# 20-RGMII_ETHERNET_PHY_-_ICSSG_PRG2_PRU0.net
KiCad netlist of a schematic drawn in Altium Designer
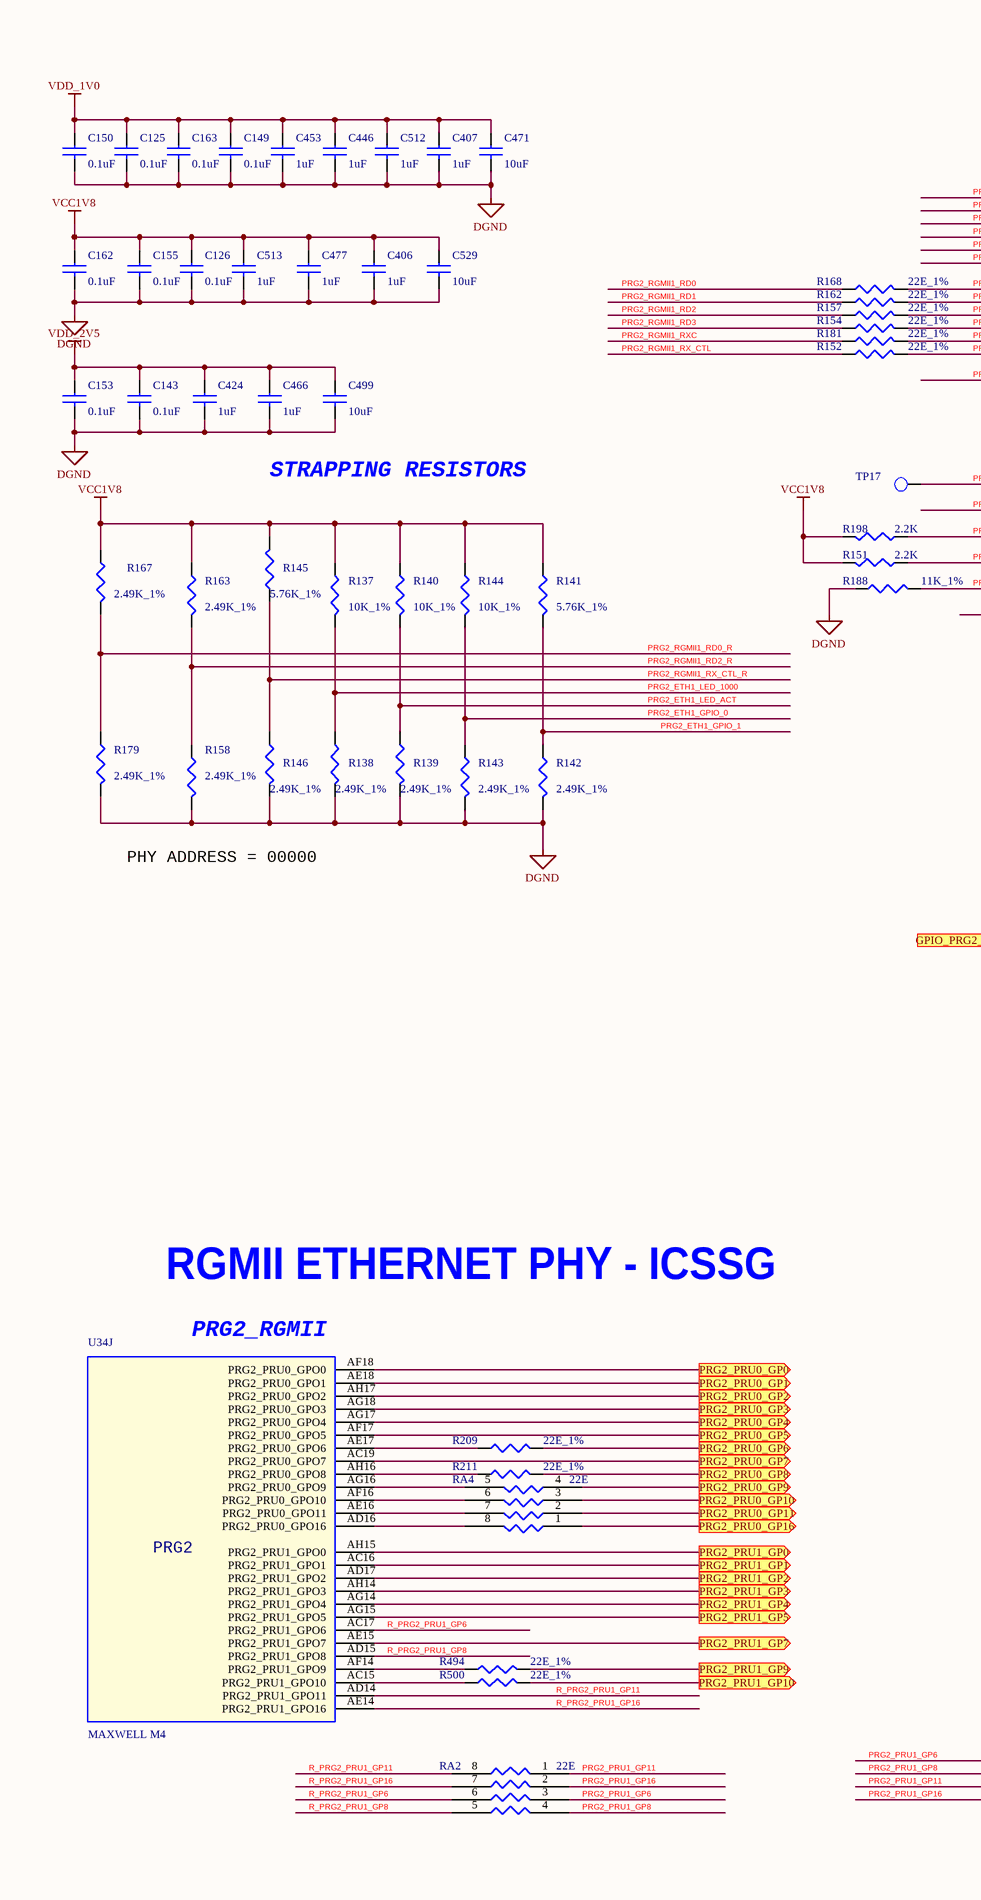
[diagram p0: 20-RGMII ETHERNET PHY - ICSSG PRG2_PRU0.SchDoc, left]
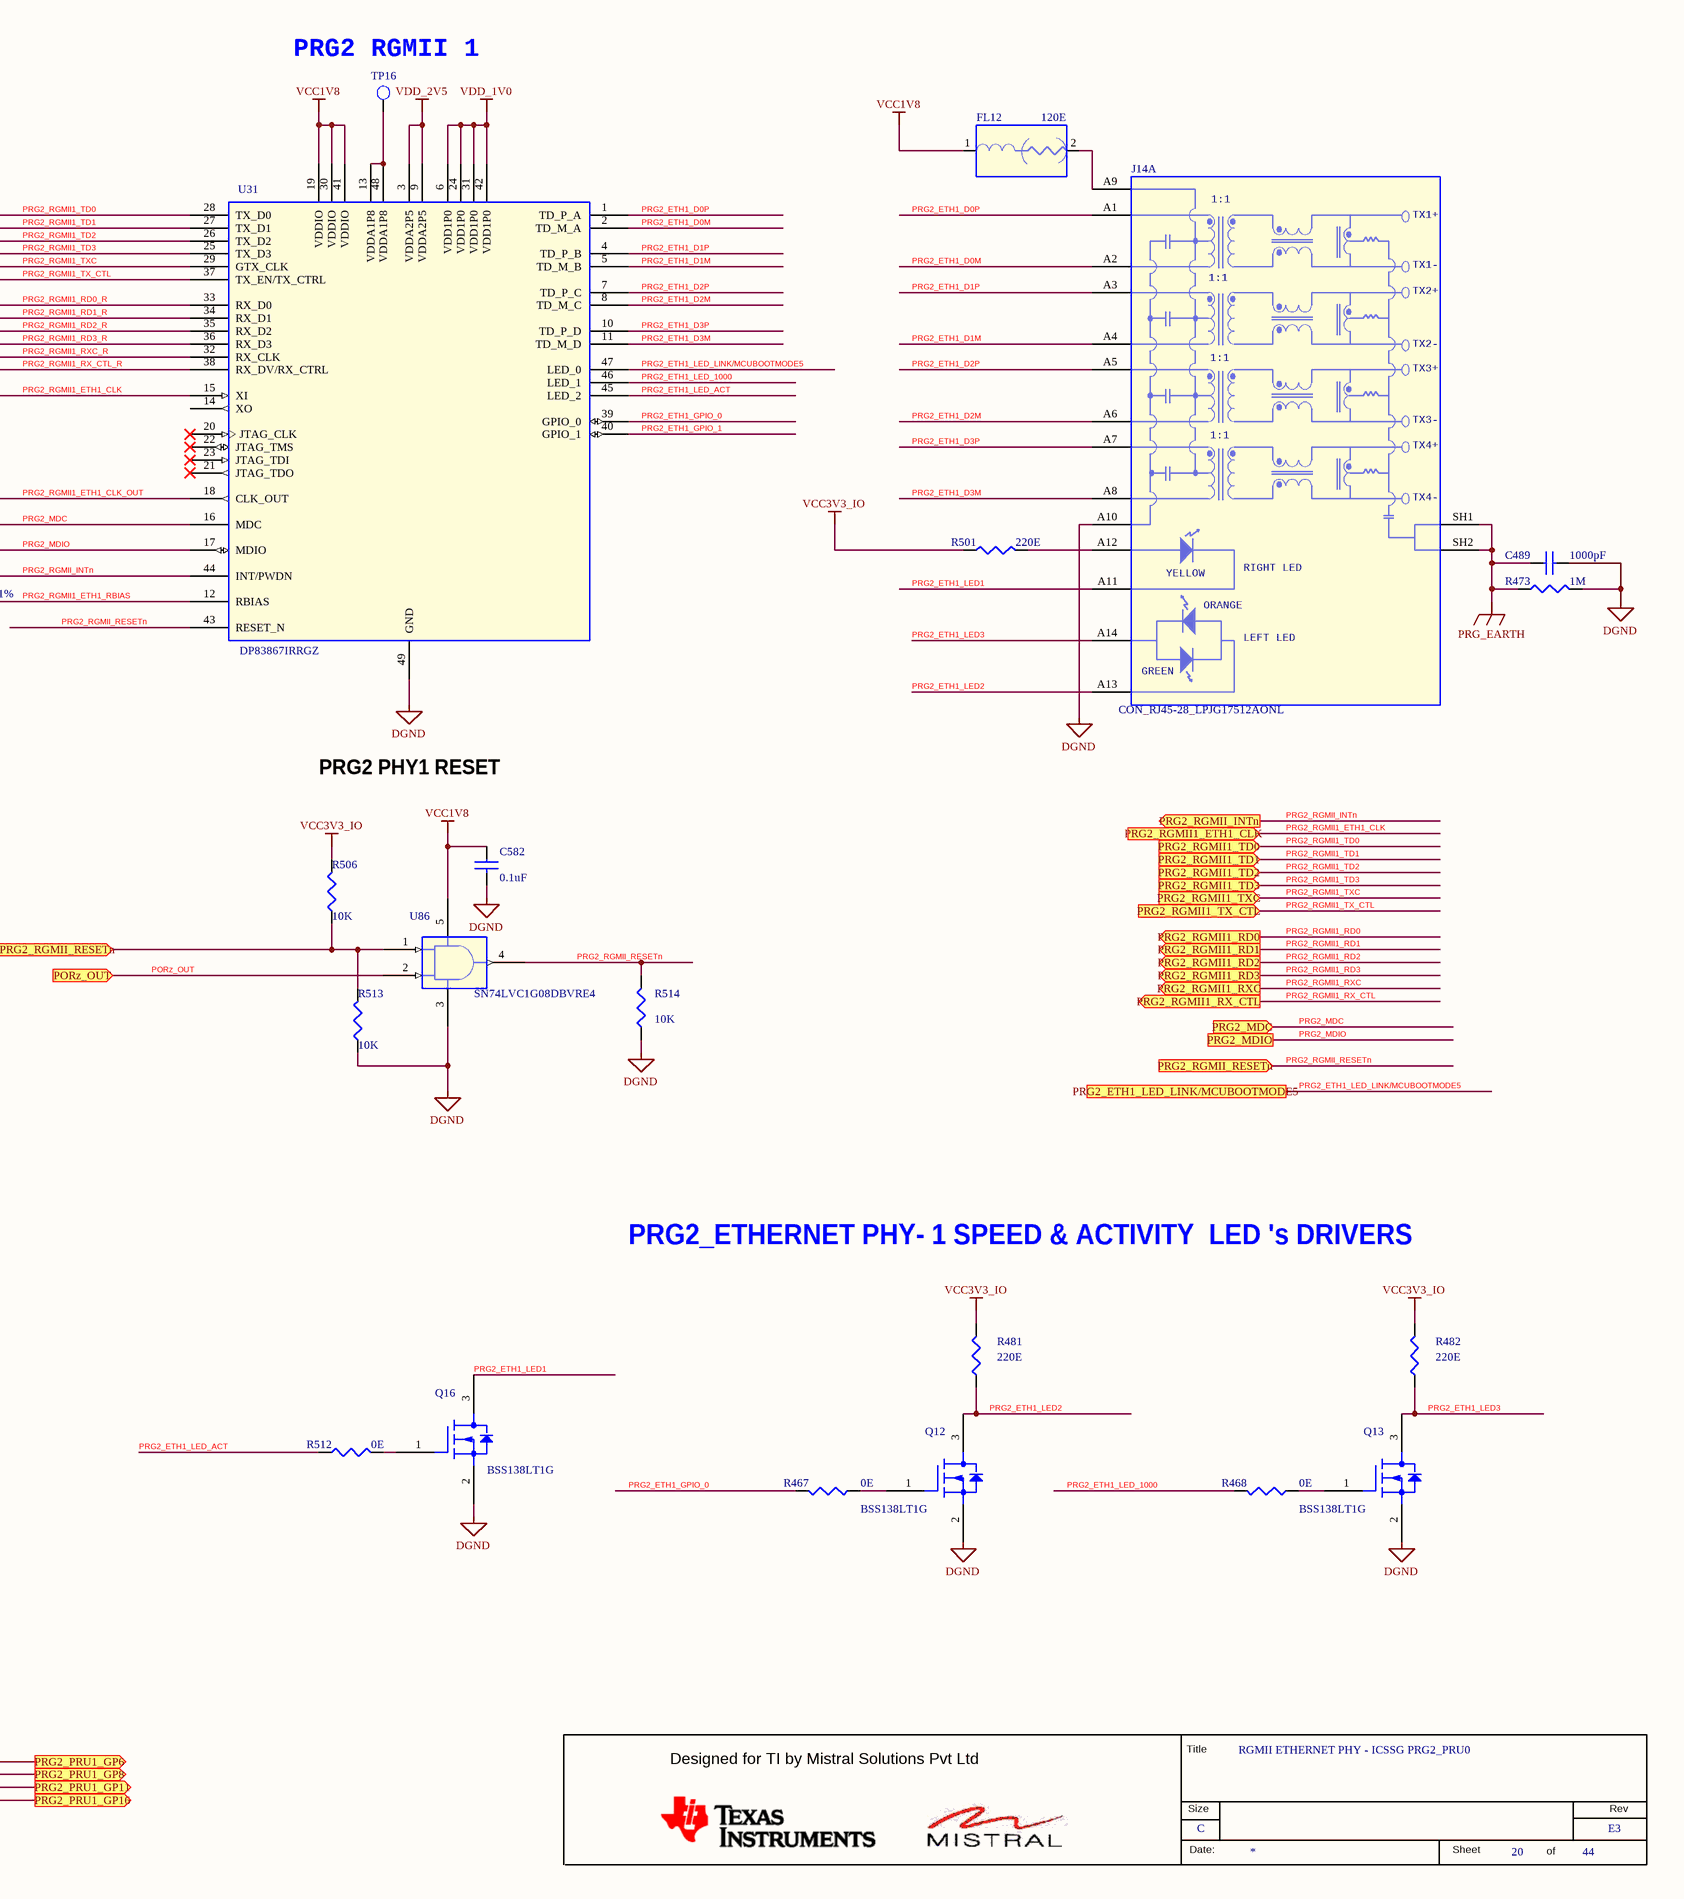
[diagram p1: 20-RGMII ETHERNET PHY - ICSSG PRG2_PRU0.SchDoc, right]

(export (version "E")
  (design (tool "Eeschema 10.0.6"))
  (components
    (comp (ref "C125")
      (value "0.1uF")
      (footprint "CAP0201_0-5")
      (description "CAP CERAMIC 0.1uF 16V 10% X5R 0201")
      (fields (field (name "DISTRIBUTOR_PART_NUMBER") "490-16742-1-ND") (field (name "VOLTAGE") "16V"))
      (libsource (lib "*") (part "CAP_Dup5"))
    )
    (comp (ref "C126")
      (value "0.1uF")
      (footprint "CAP0201_0-5")
      (description "CAP CERAMIC 0.1uF 16V 10% X5R 0201")
      (fields
        (field (name "MISTRAL PART NO") "120009030072-R")
        (field (name "MFR_PART_NUMBER") "GRM033R61C104KE84J")
      )
      (libsource (lib "*") (part "CAP_Dup5"))
    )
    (comp (ref "C143")
      (value "0.1uF")
      (footprint "CAP0201_0-5")
      (description "CAP CERAMIC 0.1uF 16V 10% X5R 0201")
      (fields
        (field (name "MISTRAL PART NO") "120009030072-R")
        (field (name "MFR_PART_NUMBER") "GRM033R61C104KE84J")
      )
      (libsource (lib "*") (part "CAP_Dup5"))
    )
    (comp (ref "C149")
      (value "0.1uF")
      (footprint "CAP0201_0-5")
      (description "CAP CERAMIC 0.1uF 16V 10% X5R 0201")
      (fields
        (field (name "MISTRAL PART NO") "120009030072-R")
        (field (name "MFR_PART_NUMBER") "GRM033R61C104KE84J")
      )
      (libsource (lib "*") (part "CAP_Dup5"))
    )
    (comp (ref "C150")
      (value "0.1uF")
      (footprint "CAP0201_0-5")
      (description "CAP CERAMIC 0.1uF 16V 10% X5R 0201")
      (fields (field (name "DISTRIBUTOR_PART_NUMBER") "490-16742-1-ND") (field (name "VOLTAGE") "16V"))
      (libsource (lib "*") (part "CAP_Dup5"))
    )
    (comp (ref "C153")
      (value "0.1uF")
      (footprint "CAP0201_0-5")
      (description "CAP CERAMIC 0.1uF 16V 10% X5R 0201")
      (fields (field (name "DISTRIBUTOR_PART_NUMBER") "490-16742-1-ND") (field (name "VOLTAGE") "16V"))
      (libsource (lib "*") (part "CAP_Dup5"))
    )
    (comp (ref "C155")
      (value "0.1uF")
      (footprint "CAP0201_0-5")
      (description "CAP CERAMIC 0.1uF 16V 10% X5R 0201")
      (fields
        (field (name "MISTRAL PART NO") "120009030072-R")
        (field (name "MFR_PART_NUMBER") "GRM033R61C104KE84J")
      )
      (libsource (lib "*") (part "CAP_Dup5"))
    )
    (comp (ref "C162")
      (value "0.1uF")
      (footprint "CAP0201_0-5")
      (description "CAP CERAMIC 0.1uF 16V 10% X5R 0201")
      (fields
        (field (name "MISTRAL PART NO") "120009030072-R")
        (field (name "MFR_PART_NUMBER") "GRM033R61C104KE84J")
      )
      (libsource (lib "*") (part "CAP_Dup5"))
    )
    (comp (ref "C163")
      (value "0.1uF")
      (footprint "CAP0201_0-5")
      (description "CAP CERAMIC 0.1uF 16V 10% X5R 0201")
      (fields
        (field (name "MISTRAL PART NO") "120009030072-R")
        (field (name "MFR_PART_NUMBER") "GRM033R61C104KE84J")
      )
      (libsource (lib "*") (part "CAP_Dup5"))
    )
    (comp (ref "C406")
      (value "1uF")
      (footprint "CAP0402_0-75")
      (description "CAP CERAMIC 1uF 16V 20% X5R 0402")
      (fields
        (field (name "MISTRAL PART NO") "120018020006-R")
        (field (name "MFR_PART_NUMBER") "EMK105BJ105MV-F")
      )
      (libsource (lib "*") (part "CAP_Dup5"))
    )
    (comp (ref "C407")
      (value "1uF")
      (footprint "CAP0402_0-75")
      (description "CAP CERAMIC 1uF 16V 20% X5R 0402")
      (fields
        (field (name "MISTRAL PART NO") "120018020006-R")
        (field (name "MFR_PART_NUMBER") "EMK105BJ105MV-F")
      )
      (libsource (lib "*") (part "CAP_Dup5"))
    )
    (comp (ref "C424")
      (value "1uF")
      (footprint "CAP0402_0-75")
      (description "CAP CERAMIC 1uF 16V 20% X5R 0402")
      (fields (field (name "DISTRIBUTOR_PART_NUMBER") "587-5514-1-ND") (field (name "VOLTAGE") "16V"))
      (libsource (lib "*") (part "CAP_Dup5"))
    )
    (comp (ref "C446")
      (value "1uF")
      (footprint "CAP0402_0-75")
      (description "CAP CERAMIC 1uF 16V 20% X5R 0402")
      (fields
        (field (name "MISTRAL PART NO") "120018020006-R")
        (field (name "MFR_PART_NUMBER") "EMK105BJ105MV-F")
      )
      (libsource (lib "*") (part "CAP_Dup5"))
    )
    (comp (ref "C453")
      (value "1uF")
      (footprint "CAP0402_0-75")
      (description "CAP CERAMIC 1uF 16V 20% X5R 0402")
      (fields (field (name "DISTRIBUTOR_PART_NUMBER") "587-5514-1-ND") (field (name "VOLTAGE") "16V"))
      (libsource (lib "*") (part "CAP_Dup5"))
    )
    (comp (ref "C466")
      (value "1uF")
      (footprint "CAP0402_0-75")
      (description "CAP CERAMIC 1uF 16V 20% X5R 0402")
      (fields (field (name "DISTRIBUTOR_PART_NUMBER") "587-5514-1-ND") (field (name "VOLTAGE") "16V"))
      (libsource (lib "*") (part "CAP_Dup5"))
    )
    (comp (ref "C471")
      (value "10uF")
      (footprint "CAP0603_1")
      (description "CAP CERAMIC 10uF 10V 10% X5R 0603")
      (fields
        (field (name "MISTRAL PART NO") "120010080001-R")
        (field (name "MFR_PART_NUMBER") "0603ZD106KAT2A")
      )
      (libsource (lib "*") (part "CAP_Dup5"))
    )
    (comp (ref "C477")
      (value "1uF")
      (footprint "CAP0402_0-75")
      (description "CAP CERAMIC 1uF 16V 20% X5R 0402")
      (fields
        (field (name "MISTRAL PART NO") "120018020006-R")
        (field (name "MFR_PART_NUMBER") "EMK105BJ105MV-F")
      )
      (libsource (lib "*") (part "CAP_Dup5"))
    )
    (comp (ref "C489")
      (value "1000pF")
      (footprint "CAP1206")
      (description "CAP CERAMIC 1000pF 2KV 10% X7R 1206")
      (fields
        (field (name "MISTRAL PART NO") "120009030147-R")
        (field (name "MFR_PART_NUMBER") "1206GC102KAT1A")
      )
      (libsource (lib "*") (part "CAP_Dup5"))
    )
    (comp (ref "C499")
      (value "10uF")
      (footprint "CAP0603_1")
      (description "CAP CERAMIC 10uF 10V 10% X5R 0603")
      (fields (field (name "DISTRIBUTOR_PART_NUMBER") "478-10766-1-ND") (field (name "VOLTAGE") "10V"))
      (libsource (lib "*") (part "CAP_Dup5"))
    )
    (comp (ref "C512")
      (value "1uF")
      (footprint "CAP0402_0-75")
      (description "CAP CERAMIC 1uF 16V 20% X5R 0402")
      (fields (field (name "DISTRIBUTOR_PART_NUMBER") "587-5514-1-ND") (field (name "VOLTAGE") "16V"))
      (libsource (lib "*") (part "CAP_Dup5"))
    )
    (comp (ref "C513")
      (value "1uF")
      (footprint "CAP0402_0-75")
      (description "CAP CERAMIC 1uF 16V 20% X5R 0402")
      (fields
        (field (name "MISTRAL PART NO") "120018020006-R")
        (field (name "MFR_PART_NUMBER") "EMK105BJ105MV-F")
      )
      (libsource (lib "*") (part "CAP_Dup5"))
    )
    (comp (ref "C529")
      (value "10uF")
      (footprint "CAP0603_1")
      (description "CAP CERAMIC 10uF 10V 10% X5R 0603")
      (fields
        (field (name "MISTRAL PART NO") "120010080001-R")
        (field (name "MFR_PART_NUMBER") "0603ZD106KAT2A")
      )
      (libsource (lib "*") (part "CAP_Dup5"))
    )
    (comp (ref "C582")
      (value "0.1uF")
      (footprint "CAP0201_0-5")
      (description "CAP CERAMIC 0.1uF 16V 10% X5R 0201")
      (fields (field (name "DISTRIBUTOR_PART_NUMBER") "490-16742-1-ND") (field (name "VOLTAGE") "16V"))
      (libsource (lib "*") (part "CAP_Dup5"))
    )
    (comp (ref "FL12")
      (value "120E")
      (footprint "EMIFIL_BLM15A_0402_0-6")
      (description "FERRITE CHIP 120E 1.3A 0402")
      (fields (field (name "DISTRIBUTOR_PART_NUMBER") "490-5203-1-ND") (field (name "VOLTAGE") "NA"))
      (libsource (lib "*") (part "EMIFILTER_IND"))
    )
    (comp (ref "J14")
      (value "CON_RJ45-28_LPJG17512AONL")
      (footprint "CON_RJ45-28_LPJG17512_S_R_T_25-3")
      (description "CON JACK RJ45 28POS REGISTERED FEMALE RA TH")
      (fields (field (name "DISTRIBUTOR_PART_NUMBER") "NA") (field (name "MFR_PART_NUMBER") "LPJG17512AONL"))
      (libsource (lib "*") (part "CON_RJ45-28_LPJG17512AONL"))
    )
    (comp (ref "Q12")
      (value "BSS138LT1G")
      (footprint "SOT23-123")
      (description "IC MOSFET N-CHANNEL 50V, SOT23-3")
      (fields (field (name "DISTRIBUTOR_PART_NUMBER") "863-BSS138LT1G") (field (name "VOLTAGE") "50V"))
      (libsource (lib "*") (part "MOSFET_BSS138LT1G"))
    )
    (comp (ref "Q13")
      (value "BSS138LT1G")
      (footprint "SOT23-123")
      (description "IC MOSFET N-CHANNEL 50V, SOT23-3")
      (fields (field (name "MISTRAL PART NO") "142016040001-R") (field (name "TOLERANCE") "NA"))
      (libsource (lib "*") (part "MOSFET_BSS138LT1G"))
    )
    (comp (ref "Q16")
      (value "BSS138LT1G")
      (footprint "SOT23-123")
      (description "IC MOSFET N-CHANNEL 50V, SOT23-3")
      (fields (field (name "DISTRIBUTOR_PART_NUMBER") "863-BSS138LT1G") (field (name "VOLTAGE") "50V"))
      (libsource (lib "*") (part "MOSFET_BSS138LT1G"))
    )
    (comp (ref "R137")
      (value "10K_1%")
      (footprint "RES0402_0-5")
      (description "RES 10K 1/16W 1% 0402")
      (fields
        (field (name "MISTRAL PART NO") "110009030220-P")
        (field (name "MFR_PART_NUMBER") "RC0402FR-0710KL")
      )
      (libsource (lib "*") (part "RESISTOR_Dup5"))
    )
    (comp (ref "R138")
      (value "2.49K_1%")
      (footprint "RES0402")
      (description "RES 2.49K 1/16W 1% 0402")
      (fields
        (field (name "MISTRAL PART NO") "110016050020-R")
        (field (name "MFR_PART_NUMBER") "RC0402FR-072K49L")
      )
      (libsource (lib "*") (part "RESISTOR_Dup5"))
    )
    (comp (ref "R139")
      (value "2.49K_1%")
      (footprint "RES0402")
      (description "RES 2.49K 1/16W 1% 0402")
      (fields
        (field (name "MISTRAL PART NO") "110016050020-R")
        (field (name "MFR_PART_NUMBER") "RC0402FR-072K49L")
      )
      (libsource (lib "*") (part "RESISTOR_Dup5"))
    )
    (comp (ref "R140")
      (value "10K_1%")
      (footprint "RES0402_0-5")
      (description "RES 10K 1/16W 1% 0402")
      (fields
        (field (name "MISTRAL PART NO") "110009030220-P")
        (field (name "MFR_PART_NUMBER") "RC0402FR-0710KL")
      )
      (libsource (lib "*") (part "RESISTOR_Dup5"))
    )
    (comp (ref "R141")
      (value "5.76K_1%")
      (footprint "RES0402")
      (description "RES 5.76K 1/10W 1% 0402")
      (fields (field (name "DISTRIBUTOR_PART_NUMBER") "P5.76KLCT-ND") (field (name "TOLERANCE") "1%"))
      (libsource (lib "*") (part "RESISTOR_Dup5"))
    )
    (comp (ref "R142")
      (value "2.49K_1%")
      (footprint "RES0402")
      (description "RES 2.49K 1/16W 1% 0402")
      (fields (field (name "DISTRIBUTOR_PART_NUMBER") "311-2.49KLRCT-ND") (field (name "VOLTAGE") "NA"))
      (libsource (lib "*") (part "RESISTOR_Dup5"))
    )
    (comp (ref "R143")
      (value "2.49K_1%")
      (footprint "RES0402")
      (description "RES 2.49K 1/16W 1% 0402")
      (fields (field (name "DISTRIBUTOR_PART_NUMBER") "311-2.49KLRCT-ND") (field (name "VOLTAGE") "NA"))
      (libsource (lib "*") (part "RESISTOR_Dup5"))
    )
    (comp (ref "R144")
      (value "10K_1%")
      (footprint "RES0402_0-5")
      (description "RES 10K 1/16W 1% 0402")
      (fields (field (name "DISTRIBUTOR_PART_NUMBER") "311-10.0KLRTR-ND") (field (name "VOLTAGE") "NA"))
      (libsource (lib "*") (part "RESISTOR_Dup5"))
    )
    (comp (ref "R145")
      (value "5.76K_1%")
      (footprint "RES0402")
      (description "RES 5.76K 1/10W 1% 0402")
      (fields
        (field (name "MISTRAL PART NO") "110009030945-R")
        (field (name "MFR_PART_NUMBER") "ERJ-2RKF5761X")
      )
      (libsource (lib "*") (part "RESISTOR_Dup5"))
    )
    (comp (ref "R146")
      (value "2.49K_1%")
      (footprint "RES0402")
      (description "RES 2.49K 1/16W 1% 0402")
      (fields (field (name "DISTRIBUTOR_PART_NUMBER") "311-2.49KLRCT-ND") (field (name "VOLTAGE") "NA"))
      (libsource (lib "*") (part "RESISTOR_Dup5"))
    )
    (comp (ref "R151")
      (value "2.2K")
      (footprint "RES0402_0-5")
      (description "RES 2.2K 1/16W 5% 0402")
      (fields
        (field (name "MISTRAL PART NO") "110010120018-R")
        (field (name "MFR_PART_NUMBER") "RC0402JR-072K2L")
      )
      (libsource (lib "*") (part "RESISTOR_Dup5"))
    )
    (comp (ref "R152")
      (value "22E_1%")
      (footprint "RES0402")
      (description "RES 22E 1/16W 1% 0402")
      (fields
        (field (name "MISTRAL PART NO") "110009090004-P")
        (field (name "MFR_PART_NUMBER") "RC0402FR-0722RL")
      )
      (libsource (lib "*") (part "RESISTOR_Dup5"))
    )
    (comp (ref "R154")
      (value "22E_1%")
      (footprint "RES0402")
      (description "RES 22E 1/16W 1% 0402")
      (fields
        (field (name "CUST_PART_NUMBER") "4700-80047E")
        (field (name "DISTRIBUTOR_PART_NUMBER") "311-22.0LRCT-ND")
      )
      (libsource (lib "*") (part "RESISTOR_Dup5"))
    )
    (comp (ref "R157")
      (value "22E_1%")
      (footprint "RES0402")
      (description "RES 22E 1/16W 1% 0402")
      (fields
        (field (name "MISTRAL PART NO") "110009090004-P")
        (field (name "MFR_PART_NUMBER") "RC0402FR-0722RL")
      )
      (libsource (lib "*") (part "RESISTOR_Dup5"))
    )
    (comp (ref "R158")
      (value "2.49K_1%")
      (footprint "RES0402")
      (description "RES 2.49K 1/16W 1% 0402")
      (fields (field (name "DISTRIBUTOR_PART_NUMBER") "311-2.49KLRCT-ND") (field (name "VOLTAGE") "NA"))
      (libsource (lib "*") (part "RESISTOR_Dup5"))
    )
    (comp (ref "R162")
      (value "22E_1%")
      (footprint "RES0402")
      (description "RES 22E 1/16W 1% 0402")
      (fields
        (field (name "CUST_PART_NUMBER") "4700-80047E")
        (field (name "DISTRIBUTOR_PART_NUMBER") "311-22.0LRCT-ND")
      )
      (libsource (lib "*") (part "RESISTOR_Dup5"))
    )
    (comp (ref "R163")
      (value "2.49K_1%")
      (footprint "RES0402")
      (description "RES 2.49K 1/16W 1% 0402")
      (fields (field (name "DISTRIBUTOR_PART_NUMBER") "311-2.49KLRCT-ND") (field (name "VOLTAGE") "NA"))
      (libsource (lib "*") (part "RESISTOR_Dup5"))
    )
    (comp (ref "R167")
      (value "2.49K_1%")
      (footprint "RES0402")
      (description "RES 2.49K 1/16W 1% 0402")
      (fields (field (name "DISTRIBUTOR_PART_NUMBER") "311-2.49KLRCT-ND") (field (name "VOLTAGE") "NA"))
      (libsource (lib "*") (part "RESISTOR_Dup5"))
    )
    (comp (ref "R168")
      (value "22E_1%")
      (footprint "RES0402")
      (description "RES 22E 1/16W 1% 0402")
      (fields
        (field (name "MISTRAL PART NO") "110009090004-P")
        (field (name "MFR_PART_NUMBER") "RC0402FR-0722RL")
      )
      (libsource (lib "*") (part "RESISTOR_Dup5"))
    )
    (comp (ref "R179")
      (value "2.49K_1%")
      (footprint "RES0402")
      (description "RES 2.49K 1/16W 1% 0402")
      (fields
        (field (name "MISTRAL PART NO") "110016050020-R")
        (field (name "MFR_PART_NUMBER") "RC0402FR-072K49L")
      )
      (libsource (lib "*") (part "RESISTOR_Dup5"))
    )
    (comp (ref "R181")
      (value "22E_1%")
      (footprint "RES0402")
      (description "RES 22E 1/16W 1% 0402")
      (fields
        (field (name "CUST_PART_NUMBER") "4700-80047E")
        (field (name "DISTRIBUTOR_PART_NUMBER") "311-22.0LRCT-ND")
      )
      (libsource (lib "*") (part "RESISTOR_Dup5"))
    )
    (comp (ref "R188")
      (value "11K_1%")
      (footprint "RES0402_0-5")
      (description "RES 11K 1/16W 1% 0402")
      (fields
        (field (name "MISTRAL PART NO") "110015110012-P")
        (field (name "MFR_PART_NUMBER") "RC0402FR-0711KL")
      )
      (libsource (lib "*") (part "RESISTOR_Dup5"))
    )
    (comp (ref "R198")
      (value "2.2K")
      (footprint "RES0402_0-5")
      (description "RES 2.2K 1/16W 5% 0402")
      (fields (field (name "DISTRIBUTOR_PART_NUMBER") "311-2.2KJRCT-ND") (field (name "VOLTAGE") "NA"))
      (libsource (lib "*") (part "RESISTOR_Dup5"))
    )
    (comp (ref "R209")
      (value "22E_1%")
      (footprint "RES0402")
      (description "RES 22E 1/16W 1% 0402")
      (fields
        (field (name "MISTRAL PART NO") "110009090004-P")
        (field (name "MFR_PART_NUMBER") "RC0402FR-0722RL")
      )
      (libsource (lib "*") (part "RESISTOR_Dup5"))
    )
    (comp (ref "R211")
      (value "22E_1%")
      (footprint "RES0402")
      (description "RES 22E 1/16W 1% 0402")
      (fields
        (field (name "CUST_PART_NUMBER") "4700-80047E")
        (field (name "DISTRIBUTOR_PART_NUMBER") "311-22.0LRCT-ND")
      )
      (libsource (lib "*") (part "RESISTOR_Dup5"))
    )
    (comp (ref "R467")
      (value "0E")
      (footprint "RES0402_0-5")
      (description "RES 0E 1/16W 0402")
      (fields (field (name "DISTRIBUTOR_PART_NUMBER") "541-0.0JCT-ND") (field (name "VOLTAGE") "NA"))
      (libsource (lib "*") (part "RESISTOR_Dup4"))
    )
    (comp (ref "R468")
      (value "0E")
      (footprint "RES0402_0-5")
      (description "RES 0E 1/16W 0402")
      (fields
        (field (name "MISTRAL PART NO") "110010080019-P")
        (field (name "MFR_PART_NUMBER") "CRCW04020000Z0ED")
      )
      (libsource (lib "*") (part "RESISTOR_Dup4"))
    )
    (comp (ref "R473")
      (value "1M")
      (footprint "RES0603_0-75")
      (description "RES 1M 1/10W 5% 0603")
      (fields (field (name "DISTRIBUTOR_PART_NUMBER") "P1.0MGCT-ND") (field (name "VOLTAGE") "NA"))
      (libsource (lib "*") (part "RESISTOR_Dup5"))
    )
    (comp (ref "R481")
      (value "220E")
      (footprint "RES0402_0-5")
      (description "RES 220E 1/16W 5% 0402")
      (fields (field (name "VOLTAGE") "NA") (field (name "DISTRIBUTOR_PART_NUMBER") "P220JCT-ND"))
      (libsource (lib "*") (part "RESISTOR_Dup5"))
    )
    (comp (ref "R482")
      (value "220E")
      (footprint "RES0402_0-5")
      (description "RES 220E 1/16W 5% 0402")
      (fields (field (name "VOLTAGE") "NA") (field (name "MISTRAL PART NO") "110009030506-R"))
      (libsource (lib "*") (part "RESISTOR_Dup5"))
    )
    (comp (ref "R494")
      (value "22E_1%")
      (footprint "RES0402")
      (description "RES 22E 1/16W 1% 0402")
      (fields
        (field (name "CUST_PART_NUMBER") "4700-80047E")
        (field (name "DISTRIBUTOR_PART_NUMBER") "311-22.0LRCT-ND")
      )
      (libsource (lib "*") (part "RESISTOR_Dup5"))
    )
    (comp (ref "R500")
      (value "22E_1%")
      (footprint "RES0402")
      (description "RES 22E 1/16W 1% 0402")
      (fields
        (field (name "MISTRAL PART NO") "110009090004-P")
        (field (name "MFR_PART_NUMBER") "RC0402FR-0722RL")
      )
      (libsource (lib "*") (part "RESISTOR_Dup5"))
    )
    (comp (ref "R501")
      (value "220E")
      (footprint "RES0402_0-5")
      (description "RES 220E 1/16W 5% 0402")
      (fields (field (name "VOLTAGE") "NA") (field (name "MISTRAL PART NO") "110009030506-R"))
      (libsource (lib "*") (part "RESISTOR_Dup5"))
    )
    (comp (ref "R506")
      (value "10K")
      (footprint "RES0402_0-5")
      (description "RES 10K 1/16W 5% 0402")
      (fields
        (field (name "MISTRAL PART NO") "110009030208-R")
        (field (name "MFR_PART_NUMBER") "RC0402JR-0710KL")
      )
      (libsource (lib "*") (part "RESISTOR_Dup5"))
    )
    (comp (ref "R512")
      (value "0E")
      (footprint "RES0402_0-5")
      (description "RES 0E 1/16W 0402")
      (fields
        (field (name "MISTRAL PART NO") "110010080019-P")
        (field (name "MFR_PART_NUMBER") "CRCW04020000Z0ED")
      )
      (libsource (lib "*") (part "RESISTOR_Dup4"))
    )
    (comp (ref "R513")
      (value "10K")
      (footprint "RES0402_0-5")
      (description "RES 10K 1/16W 5% 0402")
      (fields
        (field (name "MISTRAL PART NO") "110009030208-R")
        (field (name "MFR_PART_NUMBER") "RC0402JR-0710KL")
      )
      (libsource (lib "*") (part "RESISTOR_Dup5"))
    )
    (comp (ref "R514")
      (value "10K")
      (footprint "RES0402_0-5")
      (description "RES 10K 1/16W 5% 0402")
      (fields (field (name "DISTRIBUTOR_PART_NUMBER") "311-10KJRCT-ND") (field (name "VOLTAGE") "NA"))
      (libsource (lib "*") (part "RESISTOR_Dup5"))
    )
    (comp (ref "RA2")
      (value "22E")
      (footprint "RESA_EXB28V_0402-4_0-5")
      (description "RES ARRAY 22E 31mW 5% 0402")
      (fields (field (name "DISTRIBUTOR_PART_NUMBER") "Y7220CT-ND") (field (name "VOLTAGE") "NA"))
      (libsource (lib "*") (part "RESARR_ISO4"))
    )
    (comp (ref "RA4")
      (value "22E")
      (footprint "RESA_EXB28V_0402-4_0-5")
      (description "RES ARRAY 22E 31mW 5% 0402")
      (fields (field (name "DISTRIBUTOR_PART_NUMBER") "Y7220CT-ND") (field (name "VOLTAGE") "NA"))
      (libsource (lib "*") (part "RESARR_ISO4"))
    )
    (comp (ref "TP16")
      (value "TP40_SMD")
      (footprint "TP40_SMD")
      (description "TESTPOINT CIR 40 SMD")
      (fields (field (name "VOLTAGE") "NA") (field (name "MISTRAL PART NO") "130009030933"))
      (libsource (lib "*") (part "TESTPOINT"))
    )
    (comp (ref "TP17")
      (value "TP40_SMD")
      (footprint "TP40_SMD")
      (description "TESTPOINT CIR 40 SMD")
      (fields (field (name "DISTRIBUTOR_PART_NUMBER") "NA") (field (name "MISTRAL PART NO") "130009030933"))
      (libsource (lib "*") (part "TESTPOINT"))
    )
    (comp (ref "U31")
      (value "DP83867IRRGZ")
      (footprint "QFN48_19-68_280X280_1")
      (description "IC HIGH IMMUNITY 10/100/1000 Mb/s ETHERNET PHY LAYER TRANSCEIVER VQFN48")
      (fields (field (name "DISTRIBUTOR_PART_NUMBER") "DP83867IRRGZT-ND") (field (name "VOLTAGE") "NA"))
      (libsource (lib "*") (part "DP83867IRRGZ_VQFN48"))
    )
    (comp (ref "U34")
      (value "MAXWELL M4")
      (footprint "BGA784_31-49_910X910_1-7")
      (description "IC MAXWELL MICRO CONTROLLER UNIT BGA784")
      (fields (field (name "DISTRIBUTOR_PART_NUMBER") "NA") (field (name "MFR_PART_NUMBER") "MAXWELL M4_EVM"))
      (libsource (lib "*") (part "AM654X_BGA784"))
    )
    (comp (ref "U86")
      (value "SN74LVC1G08DBVRE4")
      (footprint "SOT23-5")
      (description "IC SINGLE 2-INPUT POSITIVE AND GATE SOT23-5")
      (fields
        (field (name "DISTRIBUTOR_PART_NUMBER") "SN74LVC1G08DBVRE4-ND")
        (field (name "MISTRAL PART NO") "141009060026-R")
      )
      (libsource (lib "*") (part "SN74LVC1G08DBVRE4_SOT23-5"))
    )
  )
  (nets
    (net (code "1") (name "/GPIO_PRG2_RGMII_RESETn") (class "Default")
      (node (ref "R506") (pin "1") (pinfunction "1_1") (pintype "passive"))
      (node (ref "R513") (pin "2") (pinfunction "2_2") (pintype "passive"))
      (node (ref "U86") (pin "1") (pinfunction "A_1") (pintype "input"))
    )
    (net (code "2") (name "/PORz_OUT") (class "Default")
      (node (ref "U86") (pin "2") (pinfunction "B_2") (pintype "input"))
    )
    (net (code "3") (name "/PRG2_ETH1_D0M") (class "Default")
      (node (ref "J14") (pin "A2") (pinfunction "TD1-_1_A2") (pintype "passive"))
      (node (ref "U31") (pin "2") (pinfunction "TD_M_A_2") (pintype "passive"))
    )
    (net (code "4") (name "/PRG2_ETH1_D0P") (class "Default")
      (node (ref "J14") (pin "A1") (pinfunction "TD1+_1_A1") (pintype "passive"))
      (node (ref "U31") (pin "1") (pinfunction "TD_P_A_1") (pintype "passive"))
    )
    (net (code "5") (name "/PRG2_ETH1_D1M") (class "Default")
      (node (ref "J14") (pin "A4") (pinfunction "TD2-_1_A4") (pintype "passive"))
      (node (ref "U31") (pin "5") (pinfunction "TD_M_B_5") (pintype "passive"))
    )
    (net (code "6") (name "/PRG2_ETH1_D1P") (class "Default")
      (node (ref "J14") (pin "A3") (pinfunction "TD2+_1_A3") (pintype "passive"))
      (node (ref "U31") (pin "4") (pinfunction "TD_P_B_4") (pintype "passive"))
    )
    (net (code "7") (name "/PRG2_ETH1_D2M") (class "Default")
      (node (ref "J14") (pin "A6") (pinfunction "TD3-_1_A6") (pintype "passive"))
      (node (ref "U31") (pin "8") (pinfunction "TD_M_C_8") (pintype "passive"))
    )
    (net (code "8") (name "/PRG2_ETH1_D2P") (class "Default")
      (node (ref "J14") (pin "A5") (pinfunction "TD3+_1_A5") (pintype "passive"))
      (node (ref "U31") (pin "7") (pinfunction "TD_P_C_7") (pintype "passive"))
    )
    (net (code "9") (name "/PRG2_ETH1_D3M") (class "Default")
      (node (ref "J14") (pin "A8") (pinfunction "TD4-_1_A8") (pintype "passive"))
      (node (ref "U31") (pin "11") (pinfunction "TD_M_D_11") (pintype "passive"))
    )
    (net (code "10") (name "/PRG2_ETH1_D3P") (class "Default")
      (node (ref "J14") (pin "A7") (pinfunction "TD4+_1_A7") (pintype "passive"))
      (node (ref "U31") (pin "10") (pinfunction "TD_P_D_10") (pintype "passive"))
    )
    (net (code "11") (name "/PRG2_ETH1_GPIO_0") (class "Default")
      (node (ref "R143") (pin "1") (pinfunction "1_1") (pintype "passive"))
      (node (ref "R144") (pin "2") (pinfunction "2_2") (pintype "passive"))
      (node (ref "R467") (pin "2") (pinfunction "2_2") (pintype "passive"))
      (node (ref "U31") (pin "39") (pinfunction "GPIO_0_39") (pintype "bidirectional"))
    )
    (net (code "12") (name "/PRG2_ETH1_GPIO_1") (class "Default")
      (node (ref "R141") (pin "2") (pinfunction "2_2") (pintype "passive"))
      (node (ref "R142") (pin "1") (pinfunction "1_1") (pintype "passive"))
      (node (ref "U31") (pin "40") (pinfunction "GPIO_1_40") (pintype "bidirectional"))
    )
    (net (code "13") (name "/PRG2_ETH1_LED1") (class "Default")
      (node (ref "J14") (pin "A11") (pinfunction "A11_A11") (pintype "passive"))
      (node (ref "Q16") (pin "3") (pinfunction "D_3") (pintype "passive"))
    )
    (net (code "14") (name "/PRG2_ETH1_LED2") (class "Default")
      (node (ref "J14") (pin "A13") (pinfunction "A13_A13") (pintype "passive"))
      (node (ref "Q12") (pin "3") (pinfunction "D_3") (pintype "passive"))
      (node (ref "R481") (pin "1") (pinfunction "1_1") (pintype "passive"))
    )
    (net (code "15") (name "/PRG2_ETH1_LED3") (class "Default")
      (node (ref "J14") (pin "A14") (pinfunction "A14_A14") (pintype "passive"))
      (node (ref "Q13") (pin "3") (pinfunction "D_3") (pintype "passive"))
      (node (ref "R482") (pin "1") (pinfunction "1_1") (pintype "passive"))
    )
    (net (code "16") (name "/PRG2_ETH1_LED_1000") (class "Default")
      (node (ref "R137") (pin "2") (pinfunction "2_2") (pintype "passive"))
      (node (ref "R138") (pin "1") (pinfunction "1_1") (pintype "passive"))
      (node (ref "R468") (pin "2") (pinfunction "2_2") (pintype "passive"))
      (node (ref "U31") (pin "46") (pinfunction "LED_1_46") (pintype "passive"))
    )
    (net (code "17") (name "/PRG2_ETH1_LED_ACT") (class "Default")
      (node (ref "R139") (pin "1") (pinfunction "1_1") (pintype "passive"))
      (node (ref "R140") (pin "2") (pinfunction "2_2") (pintype "passive"))
      (node (ref "R512") (pin "1") (pinfunction "1_1") (pintype "passive"))
      (node (ref "U31") (pin "45") (pinfunction "LED_2_45") (pintype "passive"))
    )
    (net (code "18") (name "/PRG2_ETH1_LED_LINK{slash}MCUBOOTMODE5") (class "Default")
      (node (ref "U31") (pin "47") (pinfunction "LED_0_47") (pintype "passive"))
    )
    (net (code "19") (name "/PRG2_MDC") (class "Default")
      (node (ref "U31") (pin "16") (pinfunction "MDC_16") (pintype "passive"))
    )
    (net (code "20") (name "/PRG2_MDIO") (class "Default")
      (node (ref "R198") (pin "1") (pinfunction "1_1") (pintype "passive"))
      (node (ref "U31") (pin "17") (pinfunction "MDIO_17") (pintype "bidirectional"))
    )
    (net (code "21") (name "/PRG2_PRU0_GP0") (class "Default")
      (node (ref "U34") (pin "AF18") (pinfunction "PRG2_PRU0_GPO0_AF18") (pintype "passive"))
    )
    (net (code "22") (name "/PRG2_PRU0_GP1") (class "Default")
      (node (ref "U34") (pin "AE18") (pinfunction "PRG2_PRU0_GPO1_AE18") (pintype "passive"))
    )
    (net (code "23") (name "/PRG2_PRU0_GP2") (class "Default")
      (node (ref "U34") (pin "AH17") (pinfunction "PRG2_PRU0_GPO2_AH17") (pintype "passive"))
    )
    (net (code "24") (name "/PRG2_PRU0_GP3") (class "Default")
      (node (ref "U34") (pin "AG18") (pinfunction "PRG2_PRU0_GPO3_AG18") (pintype "passive"))
    )
    (net (code "25") (name "/PRG2_PRU0_GP4") (class "Default")
      (node (ref "U34") (pin "AG17") (pinfunction "PRG2_PRU0_GPO4_AG17") (pintype "passive"))
    )
    (net (code "26") (name "/PRG2_PRU0_GP5") (class "Default")
      (node (ref "U34") (pin "AF17") (pinfunction "PRG2_PRU0_GPO5_AF17") (pintype "passive"))
    )
    (net (code "27") (name "/PRG2_PRU0_GP6") (class "Default")
      (node (ref "R209") (pin "2") (pinfunction "2_2") (pintype "passive"))
    )
    (net (code "28") (name "/PRG2_PRU0_GP7") (class "Default")
      (node (ref "U34") (pin "AC19") (pinfunction "PRG2_PRU0_GPO7_AC19") (pintype "passive"))
    )
    (net (code "29") (name "/PRG2_PRU0_GP8") (class "Default")
      (node (ref "R211") (pin "2") (pinfunction "2_2") (pintype "passive"))
    )
    (net (code "30") (name "/PRG2_PRU0_GP9") (class "Default")
      (node (ref "RA4") (pin "4") (pinfunction "4_4") (pintype "passive"))
    )
    (net (code "31") (name "/PRG2_PRU0_GP10") (class "Default")
      (node (ref "RA4") (pin "3") (pinfunction "3_3") (pintype "passive"))
    )
    (net (code "32") (name "/PRG2_PRU0_GP11") (class "Default")
      (node (ref "RA4") (pin "2") (pinfunction "2_2") (pintype "passive"))
    )
    (net (code "33") (name "/PRG2_PRU0_GP16") (class "Default")
      (node (ref "RA4") (pin "1") (pinfunction "1_1") (pintype "passive"))
    )
    (net (code "34") (name "/PRG2_PRU1_GP0") (class "Default")
      (node (ref "U34") (pin "AH15") (pinfunction "PRG2_PRU1_GPO0_AH15") (pintype "passive"))
    )
    (net (code "35") (name "/PRG2_PRU1_GP1") (class "Default")
      (node (ref "U34") (pin "AC16") (pinfunction "PRG2_PRU1_GPO1_AC16") (pintype "passive"))
    )
    (net (code "36") (name "/PRG2_PRU1_GP2") (class "Default")
      (node (ref "U34") (pin "AD17") (pinfunction "PRG2_PRU1_GPO2_AD17") (pintype "passive"))
    )
    (net (code "37") (name "/PRG2_PRU1_GP3") (class "Default")
      (node (ref "U34") (pin "AH14") (pinfunction "PRG2_PRU1_GPO3_AH14") (pintype "passive"))
    )
    (net (code "38") (name "/PRG2_PRU1_GP4") (class "Default")
      (node (ref "U34") (pin "AG14") (pinfunction "PRG2_PRU1_GPO4_AG14") (pintype "passive"))
    )
    (net (code "39") (name "/PRG2_PRU1_GP5") (class "Default")
      (node (ref "U34") (pin "AG15") (pinfunction "PRG2_PRU1_GPO5_AG15") (pintype "passive"))
    )
    (net (code "40") (name "/PRG2_PRU1_GP6") (class "Default")
      (node (ref "RA2") (pin "3") (pinfunction "3_3") (pintype "passive"))
    )
    (net (code "41") (name "/PRG2_PRU1_GP7") (class "Default")
      (node (ref "U34") (pin "AE15") (pinfunction "PRG2_PRU1_GPO7_AE15") (pintype "passive"))
    )
    (net (code "42") (name "/PRG2_PRU1_GP8") (class "Default")
      (node (ref "RA2") (pin "4") (pinfunction "4_4") (pintype "passive"))
    )
    (net (code "43") (name "/PRG2_PRU1_GP9") (class "Default")
      (node (ref "R494") (pin "2") (pinfunction "2_2") (pintype "passive"))
    )
    (net (code "44") (name "/PRG2_PRU1_GP10") (class "Default")
      (node (ref "R500") (pin "2") (pinfunction "2_2") (pintype "passive"))
    )
    (net (code "45") (name "/PRG2_PRU1_GP11") (class "Default")
      (node (ref "RA2") (pin "1") (pinfunction "1_1") (pintype "passive"))
    )
    (net (code "46") (name "/PRG2_PRU1_GP16") (class "Default")
      (node (ref "RA2") (pin "2") (pinfunction "2_2") (pintype "passive"))
    )
    (net (code "47") (name "/PRG2_RGMII1_ETH1_CLK") (class "Default")
      (node (ref "U31") (pin "15") (pinfunction "XI_15") (pintype "input"))
    )
    (net (code "48") (name "/PRG2_RGMII1_ETH1_CLK_OUT") (class "Default")
      (node (ref "TP17") (pin "1") (pinfunction "TP_1") (pintype "passive"))
      (node (ref "U31") (pin "18") (pinfunction "CLK_OUT_18") (pintype "output"))
    )
    (net (code "49") (name "/PRG2_RGMII1_ETH1_RBIAS") (class "Default")
      (node (ref "R188") (pin "1") (pinfunction "1_1") (pintype "passive"))
      (node (ref "U31") (pin "12") (pinfunction "RBIAS_12") (pintype "passive"))
    )
    (net (code "50") (name "/PRG2_RGMII1_RD0") (class "Default")
      (node (ref "R168") (pin "1") (pinfunction "1_1") (pintype "passive"))
    )
    (net (code "51") (name "/PRG2_RGMII1_RD0_R") (class "Default")
      (node (ref "R167") (pin "2") (pinfunction "2_2") (pintype "passive"))
      (node (ref "R168") (pin "2") (pinfunction "2_2") (pintype "passive"))
      (node (ref "R179") (pin "1") (pinfunction "1_1") (pintype "passive"))
      (node (ref "U31") (pin "33") (pinfunction "RX_D0_33") (pintype "passive"))
    )
    (net (code "52") (name "/PRG2_RGMII1_RD1") (class "Default")
      (node (ref "R162") (pin "1") (pinfunction "1_1") (pintype "passive"))
    )
    (net (code "53") (name "/PRG2_RGMII1_RD1_R") (class "Default")
      (node (ref "R162") (pin "2") (pinfunction "2_2") (pintype "passive"))
      (node (ref "U31") (pin "34") (pinfunction "RX_D1_34") (pintype "passive"))
    )
    (net (code "54") (name "/PRG2_RGMII1_RD2") (class "Default")
      (node (ref "R157") (pin "1") (pinfunction "1_1") (pintype "passive"))
    )
    (net (code "55") (name "/PRG2_RGMII1_RD2_R") (class "Default")
      (node (ref "R157") (pin "2") (pinfunction "2_2") (pintype "passive"))
      (node (ref "R158") (pin "1") (pinfunction "1_1") (pintype "passive"))
      (node (ref "R163") (pin "2") (pinfunction "2_2") (pintype "passive"))
      (node (ref "U31") (pin "35") (pinfunction "RX_D2_35") (pintype "passive"))
    )
    (net (code "56") (name "/PRG2_RGMII1_RD3") (class "Default")
      (node (ref "R154") (pin "1") (pinfunction "1_1") (pintype "passive"))
    )
    (net (code "57") (name "/PRG2_RGMII1_RD3_R") (class "Default")
      (node (ref "R154") (pin "2") (pinfunction "2_2") (pintype "passive"))
      (node (ref "U31") (pin "36") (pinfunction "RX_D3_36") (pintype "passive"))
    )
    (net (code "58") (name "/PRG2_RGMII1_RXC") (class "Default")
      (node (ref "R181") (pin "1") (pinfunction "1_1") (pintype "passive"))
    )
    (net (code "59") (name "/PRG2_RGMII1_RXC_R") (class "Default")
      (node (ref "R181") (pin "2") (pinfunction "2_2") (pintype "passive"))
      (node (ref "U31") (pin "32") (pinfunction "RX_CLK_32") (pintype "passive"))
    )
    (net (code "60") (name "/PRG2_RGMII1_RX_CTL") (class "Default")
      (node (ref "R152") (pin "1") (pinfunction "1_1") (pintype "passive"))
    )
    (net (code "61") (name "/PRG2_RGMII1_RX_CTL_R") (class "Default")
      (node (ref "R145") (pin "1") (pinfunction "1_1") (pintype "passive"))
      (node (ref "R146") (pin "1") (pinfunction "1_1") (pintype "passive"))
      (node (ref "R152") (pin "2") (pinfunction "2_2") (pintype "passive"))
      (node (ref "U31") (pin "38") (pinfunction "RX_DV/RX_CTRL_38") (pintype "passive"))
    )
    (net (code "62") (name "/PRG2_RGMII1_TD0") (class "Default")
      (node (ref "U31") (pin "28") (pinfunction "TX_D0_28") (pintype "passive"))
    )
    (net (code "63") (name "/PRG2_RGMII1_TD1") (class "Default")
      (node (ref "U31") (pin "27") (pinfunction "TX_D1_27") (pintype "passive"))
    )
    (net (code "64") (name "/PRG2_RGMII1_TD2") (class "Default")
      (node (ref "U31") (pin "26") (pinfunction "TX_D2_26") (pintype "passive"))
    )
    (net (code "65") (name "/PRG2_RGMII1_TD3") (class "Default")
      (node (ref "U31") (pin "25") (pinfunction "TX_D3_25") (pintype "passive"))
    )
    (net (code "66") (name "/PRG2_RGMII1_TXC") (class "Default")
      (node (ref "U31") (pin "29") (pinfunction "GTX_CLK_29") (pintype "passive"))
    )
    (net (code "67") (name "/PRG2_RGMII1_TX_CTL") (class "Default")
      (node (ref "U31") (pin "37") (pinfunction "TX_EN/TX_CTRL_37") (pintype "passive"))
    )
    (net (code "68") (name "/PRG2_RGMII_INTn") (class "Default")
      (node (ref "R151") (pin "1") (pinfunction "1_1") (pintype "passive"))
      (node (ref "U31") (pin "44") (pinfunction "INT/PWDN_44") (pintype "passive"))
    )
    (net (code "69") (name "/PRG2_RGMII_RESETn") (class "Default")
      (node (ref "R514") (pin "1") (pinfunction "1_1") (pintype "passive"))
      (node (ref "U31") (pin "43") (pinfunction "RESET_N_43") (pintype "passive"))
      (node (ref "U86") (pin "4") (pinfunction "Y_4") (pintype "output"))
    )
    (net (code "70") (name "/R_PRG2_PRU1_GP6") (class "Default")
      (node (ref "RA2") (pin "6") (pinfunction "6_6") (pintype "passive"))
      (node (ref "U34") (pin "AC17") (pinfunction "PRG2_PRU1_GPO6_AC17") (pintype "passive"))
    )
    (net (code "71") (name "/R_PRG2_PRU1_GP8") (class "Default")
      (node (ref "RA2") (pin "5") (pinfunction "5_5") (pintype "passive"))
      (node (ref "U34") (pin "AD15") (pinfunction "PRG2_PRU1_GPO8_AD15") (pintype "passive"))
    )
    (net (code "72") (name "/R_PRG2_PRU1_GP11") (class "Default")
      (node (ref "RA2") (pin "8") (pinfunction "8_8") (pintype "passive"))
      (node (ref "U34") (pin "AD14") (pinfunction "PRG2_PRU1_GPO11_AD14") (pintype "passive"))
    )
    (net (code "73") (name "/R_PRG2_PRU1_GP16") (class "Default")
      (node (ref "RA2") (pin "7") (pinfunction "7_7") (pintype "passive"))
      (node (ref "U34") (pin "AE14") (pinfunction "PRG2_PRU1_GPO16_AE14") (pintype "passive"))
    )
    (net (code "74") (name "DGND") (class "Default")
      (node (ref "C125") (pin "2") (pinfunction "2_2") (pintype "passive"))
      (node (ref "C126") (pin "2") (pinfunction "2_2") (pintype "passive"))
      (node (ref "C143") (pin "2") (pinfunction "2_2") (pintype "passive"))
      (node (ref "C149") (pin "2") (pinfunction "2_2") (pintype "passive"))
      (node (ref "C150") (pin "2") (pinfunction "2_2") (pintype "passive"))
      (node (ref "C153") (pin "2") (pinfunction "2_2") (pintype "passive"))
      (node (ref "C155") (pin "2") (pinfunction "2_2") (pintype "passive"))
      (node (ref "C162") (pin "2") (pinfunction "2_2") (pintype "passive"))
      (node (ref "C163") (pin "2") (pinfunction "2_2") (pintype "passive"))
      (node (ref "C406") (pin "2") (pinfunction "2_2") (pintype "passive"))
      (node (ref "C407") (pin "2") (pinfunction "2_2") (pintype "passive"))
      (node (ref "C424") (pin "2") (pinfunction "2_2") (pintype "passive"))
      (node (ref "C446") (pin "2") (pinfunction "2_2") (pintype "passive"))
      (node (ref "C453") (pin "2") (pinfunction "2_2") (pintype "passive"))
      (node (ref "C466") (pin "2") (pinfunction "2_2") (pintype "passive"))
      (node (ref "C471") (pin "2") (pinfunction "2_2") (pintype "passive"))
      (node (ref "C477") (pin "2") (pinfunction "2_2") (pintype "passive"))
      (node (ref "C489") (pin "2") (pinfunction "2_2") (pintype "passive"))
      (node (ref "C499") (pin "2") (pinfunction "2_2") (pintype "passive"))
      (node (ref "C512") (pin "2") (pinfunction "2_2") (pintype "passive"))
      (node (ref "C513") (pin "2") (pinfunction "2_2") (pintype "passive"))
      (node (ref "C529") (pin "2") (pinfunction "2_2") (pintype "passive"))
      (node (ref "C582") (pin "2") (pinfunction "2_2") (pintype "passive"))
      (node (ref "J14") (pin "A10") (pinfunction "GND_A10") (pintype "power_in"))
      (node (ref "Q12") (pin "2") (pinfunction "S_2") (pintype "passive"))
      (node (ref "Q13") (pin "2") (pinfunction "S_2") (pintype "passive"))
      (node (ref "Q16") (pin "2") (pinfunction "S_2") (pintype "passive"))
      (node (ref "R138") (pin "2") (pinfunction "2_2") (pintype "passive"))
      (node (ref "R139") (pin "2") (pinfunction "2_2") (pintype "passive"))
      (node (ref "R142") (pin "2") (pinfunction "2_2") (pintype "passive"))
      (node (ref "R143") (pin "2") (pinfunction "2_2") (pintype "passive"))
      (node (ref "R146") (pin "2") (pinfunction "2_2") (pintype "passive"))
      (node (ref "R158") (pin "2") (pinfunction "2_2") (pintype "passive"))
      (node (ref "R179") (pin "2") (pinfunction "2_2") (pintype "passive"))
      (node (ref "R188") (pin "2") (pinfunction "2_2") (pintype "passive"))
      (node (ref "R473") (pin "2") (pinfunction "2_2") (pintype "passive"))
      (node (ref "R513") (pin "1") (pinfunction "1_1") (pintype "passive"))
      (node (ref "R514") (pin "2") (pinfunction "2_2") (pintype "passive"))
      (node (ref "U31") (pin "49") (pinfunction "GND_49") (pintype "power_in"))
      (node (ref "U86") (pin "3") (pinfunction "GND_3") (pintype "power_in"))
    )
    (net (code "75") (name "Net-(J14-PadA12)") (class "Default")
      (node (ref "J14") (pin "A12") (pinfunction "A12_A12") (pintype "passive"))
      (node (ref "R501") (pin "2") (pinfunction "2_2") (pintype "passive"))
    )
    (net (code "76") (name "Net-(J14A-VCC)") (class "Default")
      (node (ref "FL12") (pin "2") (pinfunction "2_2") (pintype "passive"))
      (node (ref "J14") (pin "A9") (pinfunction "VCC_A9") (pintype "power_in"))
    )
    (net (code "77") (name "Net-(Q12-G)") (class "Default")
      (node (ref "Q12") (pin "1") (pinfunction "G_1") (pintype "passive"))
      (node (ref "R467") (pin "1") (pinfunction "1_1") (pintype "passive"))
    )
    (net (code "78") (name "Net-(Q13-G)") (class "Default")
      (node (ref "Q13") (pin "1") (pinfunction "G_1") (pintype "passive"))
      (node (ref "R468") (pin "1") (pinfunction "1_1") (pintype "passive"))
    )
    (net (code "79") (name "Net-(Q16-G)") (class "Default")
      (node (ref "Q16") (pin "1") (pinfunction "G_1") (pintype "passive"))
      (node (ref "R512") (pin "2") (pinfunction "2_2") (pintype "passive"))
    )
    (net (code "80") (name "Net-(TP16-TP)") (class "Default")
      (node (ref "TP16") (pin "1") (pinfunction "TP_1") (pintype "passive"))
      (node (ref "U31") (pin "13") (pinfunction "VDDA1P8_13") (pintype "power_in"))
      (node (ref "U31") (pin "48") (pinfunction "VDDA1P8_48") (pintype "power_in"))
    )
    (net (code "81") (name "Net-(U34J-PRG2_PRU0_GPO6)") (class "Default")
      (node (ref "R209") (pin "1") (pinfunction "1_1") (pintype "passive"))
      (node (ref "U34") (pin "AE17") (pinfunction "PRG2_PRU0_GPO6_AE17") (pintype "passive"))
    )
    (net (code "82") (name "Net-(U34J-PRG2_PRU0_GPO8)") (class "Default")
      (node (ref "R211") (pin "1") (pinfunction "1_1") (pintype "passive"))
      (node (ref "U34") (pin "AH16") (pinfunction "PRG2_PRU0_GPO8_AH16") (pintype "passive"))
    )
    (net (code "83") (name "Net-(U34J-PRG2_PRU0_GPO9)") (class "Default")
      (node (ref "RA4") (pin "5") (pinfunction "5_5") (pintype "passive"))
      (node (ref "U34") (pin "AG16") (pinfunction "PRG2_PRU0_GPO9_AG16") (pintype "passive"))
    )
    (net (code "84") (name "Net-(U34J-PRG2_PRU0_GPO10)") (class "Default")
      (node (ref "RA4") (pin "6") (pinfunction "6_6") (pintype "passive"))
      (node (ref "U34") (pin "AF16") (pinfunction "PRG2_PRU0_GPO10_AF16") (pintype "passive"))
    )
    (net (code "85") (name "Net-(U34J-PRG2_PRU0_GPO11)") (class "Default")
      (node (ref "RA4") (pin "7") (pinfunction "7_7") (pintype "passive"))
      (node (ref "U34") (pin "AE16") (pinfunction "PRG2_PRU0_GPO11_AE16") (pintype "passive"))
    )
    (net (code "86") (name "Net-(U34J-PRG2_PRU0_GPO16)") (class "Default")
      (node (ref "RA4") (pin "8") (pinfunction "8_8") (pintype "passive"))
      (node (ref "U34") (pin "AD16") (pinfunction "PRG2_PRU0_GPO16_AD16") (pintype "passive"))
    )
    (net (code "87") (name "Net-(U34J-PRG2_PRU1_GPO9)") (class "Default")
      (node (ref "R494") (pin "1") (pinfunction "1_1") (pintype "passive"))
      (node (ref "U34") (pin "AF14") (pinfunction "PRG2_PRU1_GPO9_AF14") (pintype "passive"))
    )
    (net (code "88") (name "Net-(U34J-PRG2_PRU1_GPO10)") (class "Default")
      (node (ref "R500") (pin "1") (pinfunction "1_1") (pintype "passive"))
      (node (ref "U34") (pin "AC15") (pinfunction "PRG2_PRU1_GPO10_AC15") (pintype "passive"))
    )
    (net (code "89") (name "PRG_EARTH") (class "Default")
      (node (ref "C489") (pin "1") (pinfunction "1_1") (pintype "passive"))
      (node (ref "J14") (pin "SH1") (pinfunction "SH1_SH1") (pintype "passive"))
      (node (ref "J14") (pin "SH2") (pinfunction "SH2_SH2") (pintype "passive"))
      (node (ref "R473") (pin "1") (pinfunction "1_1") (pintype "passive"))
    )
    (net (code "90") (name "VCC1V8") (class "Default")
      (node (ref "C126") (pin "1") (pinfunction "1_1") (pintype "passive"))
      (node (ref "C155") (pin "1") (pinfunction "1_1") (pintype "passive"))
      (node (ref "C162") (pin "1") (pinfunction "1_1") (pintype "passive"))
      (node (ref "C406") (pin "1") (pinfunction "1_1") (pintype "passive"))
      (node (ref "C477") (pin "1") (pinfunction "1_1") (pintype "passive"))
      (node (ref "C513") (pin "1") (pinfunction "1_1") (pintype "passive"))
      (node (ref "C529") (pin "1") (pinfunction "1_1") (pintype "passive"))
      (node (ref "C582") (pin "1") (pinfunction "1_1") (pintype "passive"))
      (node (ref "FL12") (pin "1") (pinfunction "1_1") (pintype "passive"))
      (node (ref "R137") (pin "1") (pinfunction "1_1") (pintype "passive"))
      (node (ref "R140") (pin "1") (pinfunction "1_1") (pintype "passive"))
      (node (ref "R141") (pin "1") (pinfunction "1_1") (pintype "passive"))
      (node (ref "R144") (pin "1") (pinfunction "1_1") (pintype "passive"))
      (node (ref "R145") (pin "2") (pinfunction "2_2") (pintype "passive"))
      (node (ref "R151") (pin "2") (pinfunction "2_2") (pintype "passive"))
      (node (ref "R163") (pin "1") (pinfunction "1_1") (pintype "passive"))
      (node (ref "R167") (pin "1") (pinfunction "1_1") (pintype "passive"))
      (node (ref "R198") (pin "2") (pinfunction "2_2") (pintype "passive"))
      (node (ref "U31") (pin "19") (pinfunction "VDDIO_19") (pintype "power_in"))
      (node (ref "U31") (pin "30") (pinfunction "VDDIO_30") (pintype "power_in"))
      (node (ref "U31") (pin "41") (pinfunction "VDDIO_41") (pintype "power_in"))
      (node (ref "U86") (pin "5") (pinfunction "VCC_5") (pintype "power_in"))
    )
    (net (code "91") (name "VCC3V3_IO") (class "Default")
      (node (ref "R481") (pin "2") (pinfunction "2_2") (pintype "passive"))
      (node (ref "R482") (pin "2") (pinfunction "2_2") (pintype "passive"))
      (node (ref "R501") (pin "1") (pinfunction "1_1") (pintype "passive"))
      (node (ref "R506") (pin "2") (pinfunction "2_2") (pintype "passive"))
    )
    (net (code "92") (name "VDD_1V0") (class "Default")
      (node (ref "C125") (pin "1") (pinfunction "1_1") (pintype "passive"))
      (node (ref "C149") (pin "1") (pinfunction "1_1") (pintype "passive"))
      (node (ref "C150") (pin "1") (pinfunction "1_1") (pintype "passive"))
      (node (ref "C163") (pin "1") (pinfunction "1_1") (pintype "passive"))
      (node (ref "C407") (pin "1") (pinfunction "1_1") (pintype "passive"))
      (node (ref "C446") (pin "1") (pinfunction "1_1") (pintype "passive"))
      (node (ref "C453") (pin "1") (pinfunction "1_1") (pintype "passive"))
      (node (ref "C471") (pin "1") (pinfunction "1_1") (pintype "passive"))
      (node (ref "C512") (pin "1") (pinfunction "1_1") (pintype "passive"))
      (node (ref "U31") (pin "24") (pinfunction "VDD1P0_24") (pintype "power_in"))
      (node (ref "U31") (pin "31") (pinfunction "VDD1P0_31") (pintype "power_in"))
      (node (ref "U31") (pin "42") (pinfunction "VDD1P0_42") (pintype "power_in"))
      (node (ref "U31") (pin "6") (pinfunction "VDD1P0_6") (pintype "power_in"))
    )
    (net (code "93") (name "VDD_2V5") (class "Default")
      (node (ref "C143") (pin "1") (pinfunction "1_1") (pintype "passive"))
      (node (ref "C153") (pin "1") (pinfunction "1_1") (pintype "passive"))
      (node (ref "C424") (pin "1") (pinfunction "1_1") (pintype "passive"))
      (node (ref "C466") (pin "1") (pinfunction "1_1") (pintype "passive"))
      (node (ref "C499") (pin "1") (pinfunction "1_1") (pintype "passive"))
      (node (ref "U31") (pin "3") (pinfunction "VDDA2P5_3") (pintype "power_in"))
      (node (ref "U31") (pin "9") (pinfunction "VDDA2P5_9") (pintype "power_in"))
    )
    (net (code "94") (name "unconnected-(U31-JTAG_CLK-Pad20)") (class "Default")
      (node (ref "U31") (pin "20") (pinfunction "JTAG_CLK_20") (pintype "input+no_connect"))
    )
    (net (code "95") (name "unconnected-(U31-JTAG_TDI-Pad23)") (class "Default")
      (node (ref "U31") (pin "23") (pinfunction "JTAG_TDI_23") (pintype "input+no_connect"))
    )
    (net (code "96") (name "unconnected-(U31-JTAG_TDO-Pad21)") (class "Default")
      (node (ref "U31") (pin "21") (pinfunction "JTAG_TDO_21") (pintype "output+no_connect"))
    )
    (net (code "97") (name "unconnected-(U31-JTAG_TMS-Pad22)") (class "Default")
      (node (ref "U31") (pin "22") (pinfunction "JTAG_TMS_22") (pintype "bidirectional+no_connect"))
    )
    (net (code "98") (name "unconnected-(U31-XO-Pad14)") (class "Default")
      (node (ref "U31") (pin "14") (pinfunction "XO_14") (pintype "output"))
    )
  )
)
